# 04__EFR32_Signal_Assign.net
KiCad netlist of a schematic drawn in Altium Designer
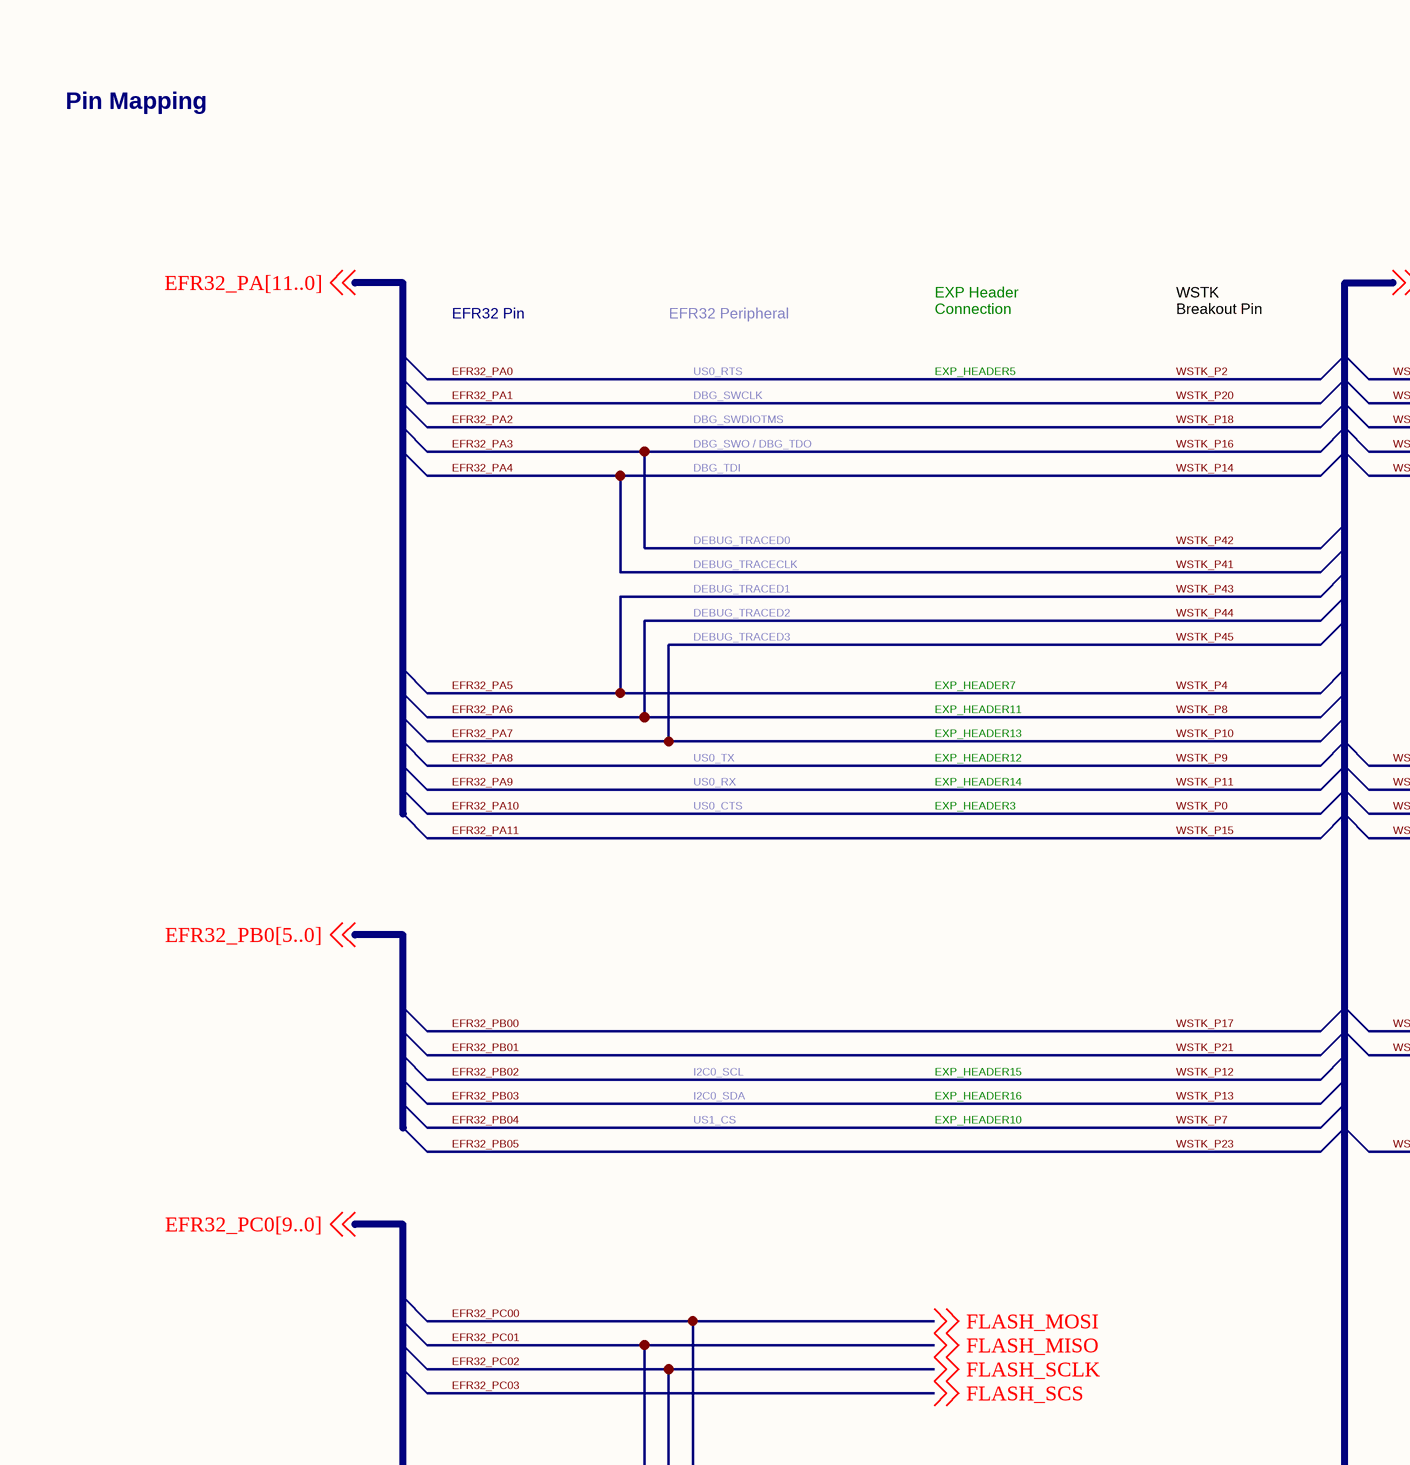
[diagram p0: 04_ EFR32 Signal Assign.SchDoc, top left]
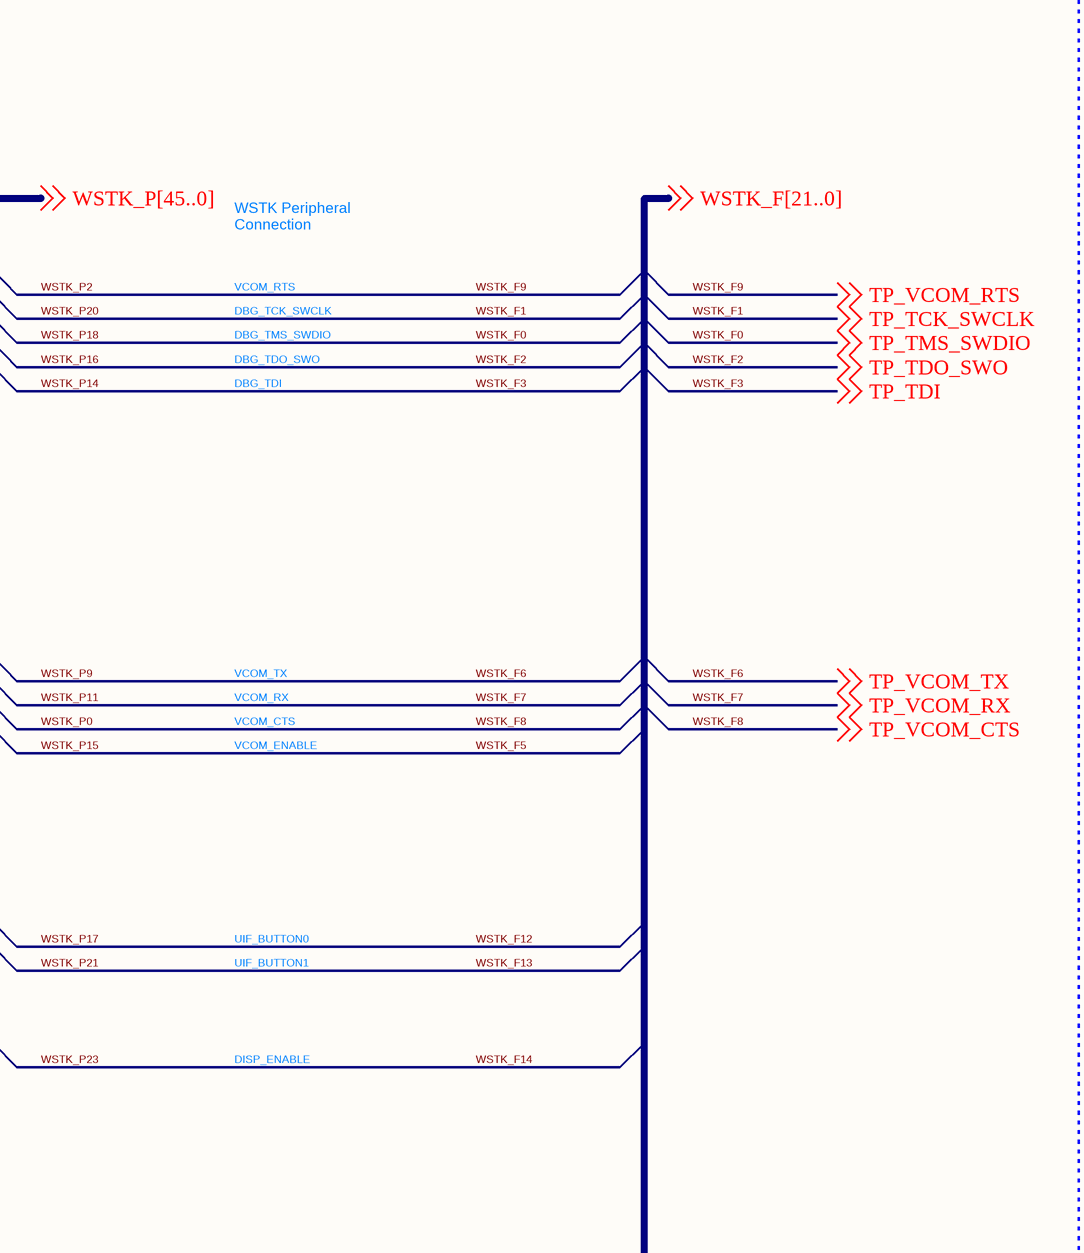
[diagram p1: 04_ EFR32 Signal Assign.SchDoc, top middle]
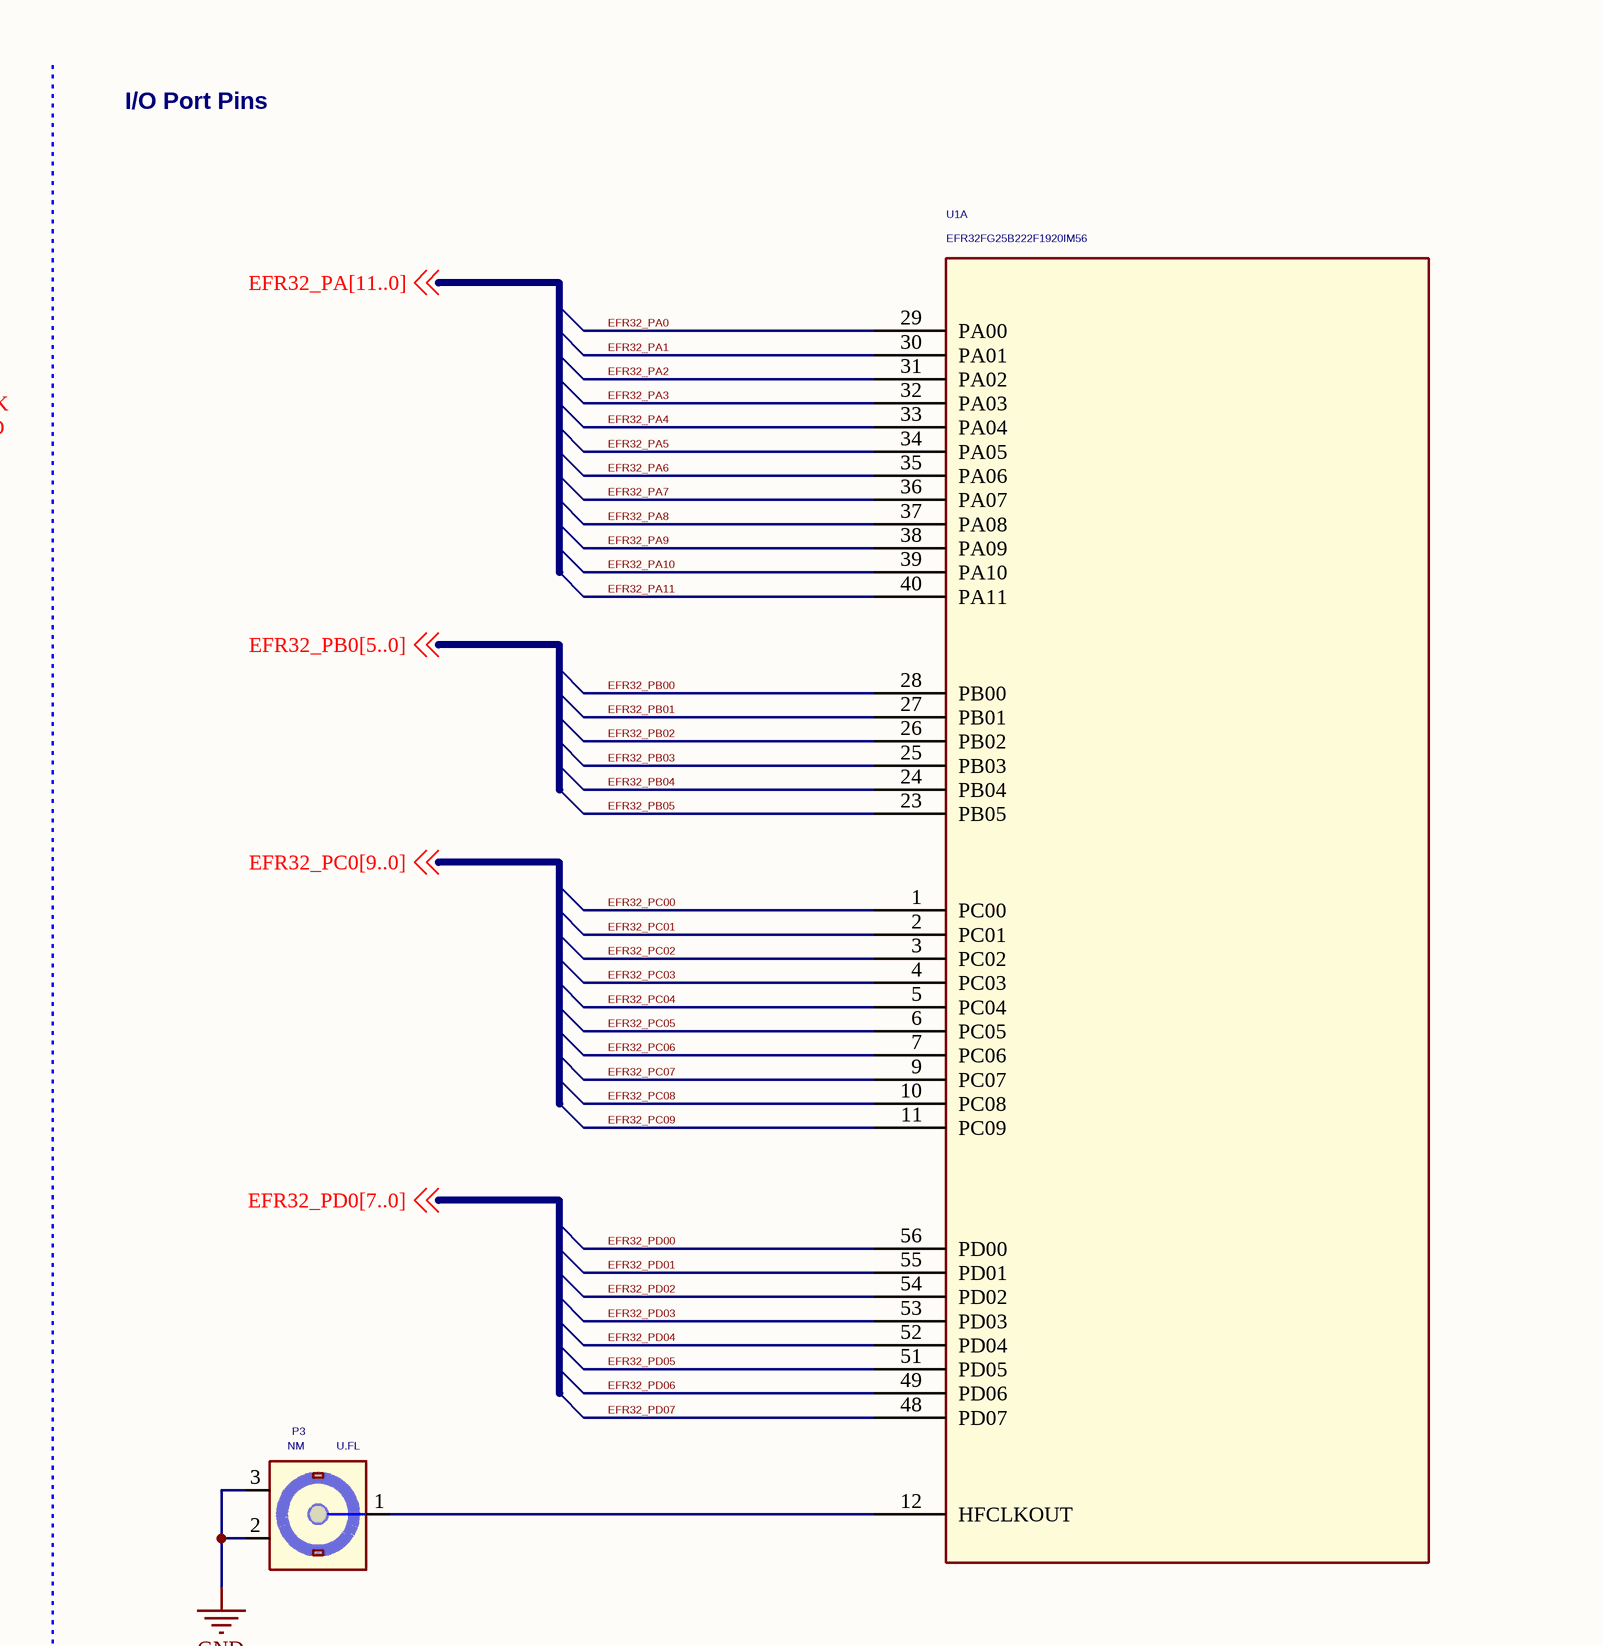
[diagram p2: 04_ EFR32 Signal Assign.SchDoc, top right]
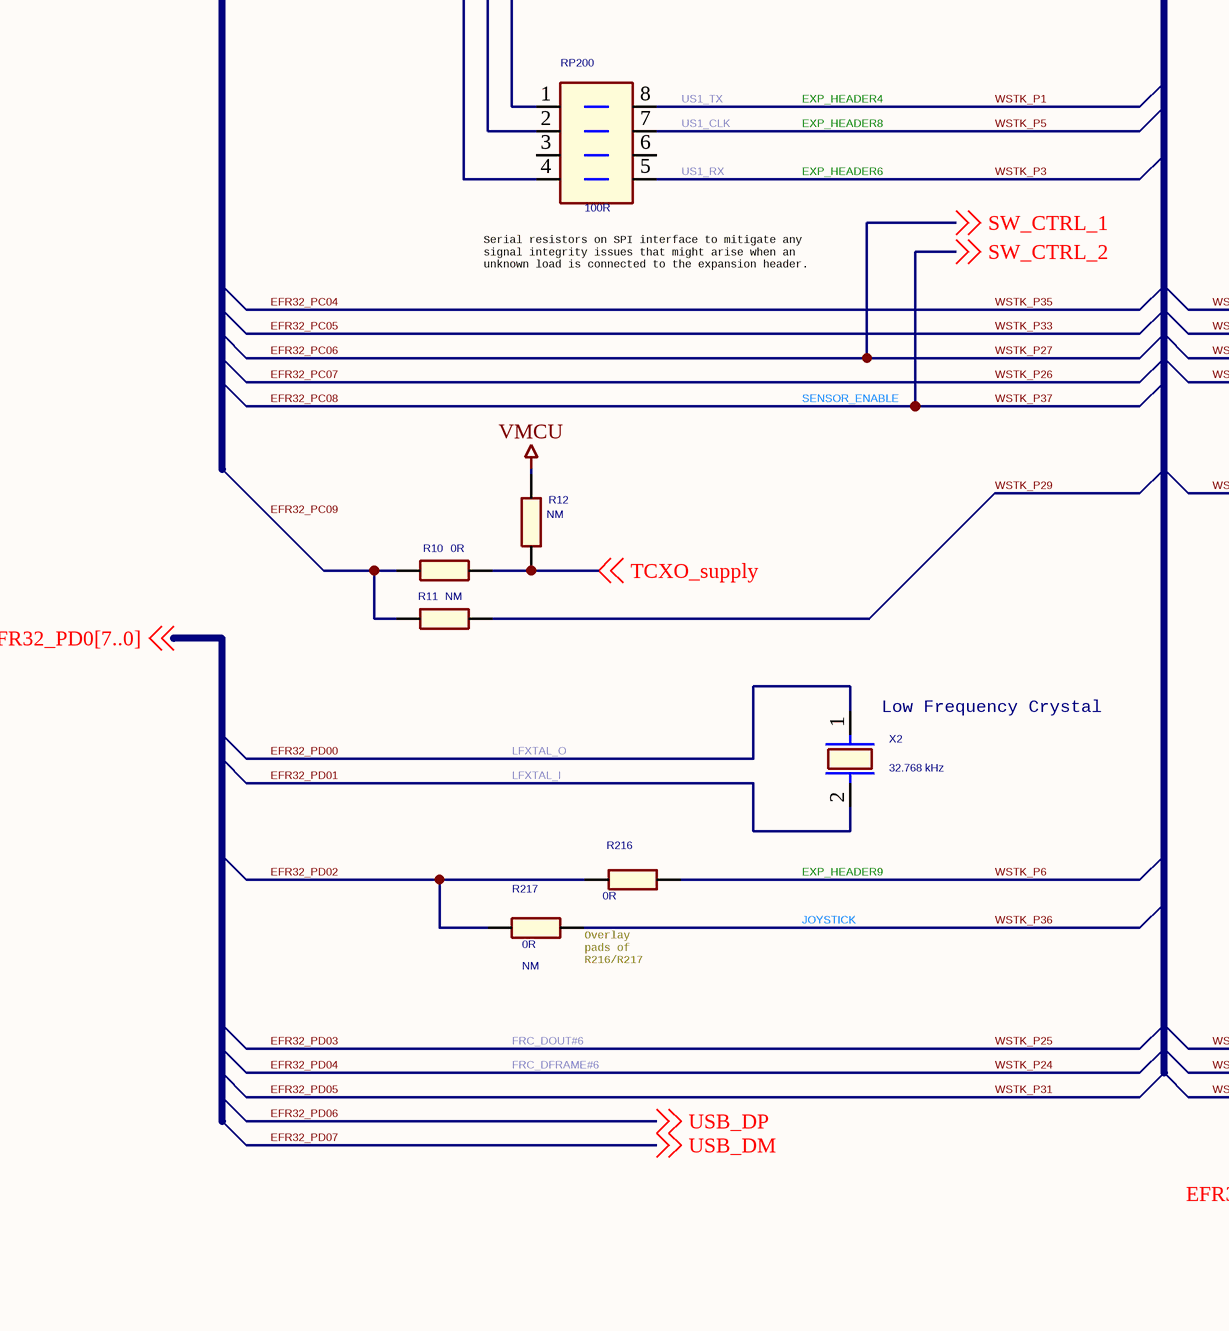
[diagram p3: 04_ EFR32 Signal Assign.SchDoc, bottom left]
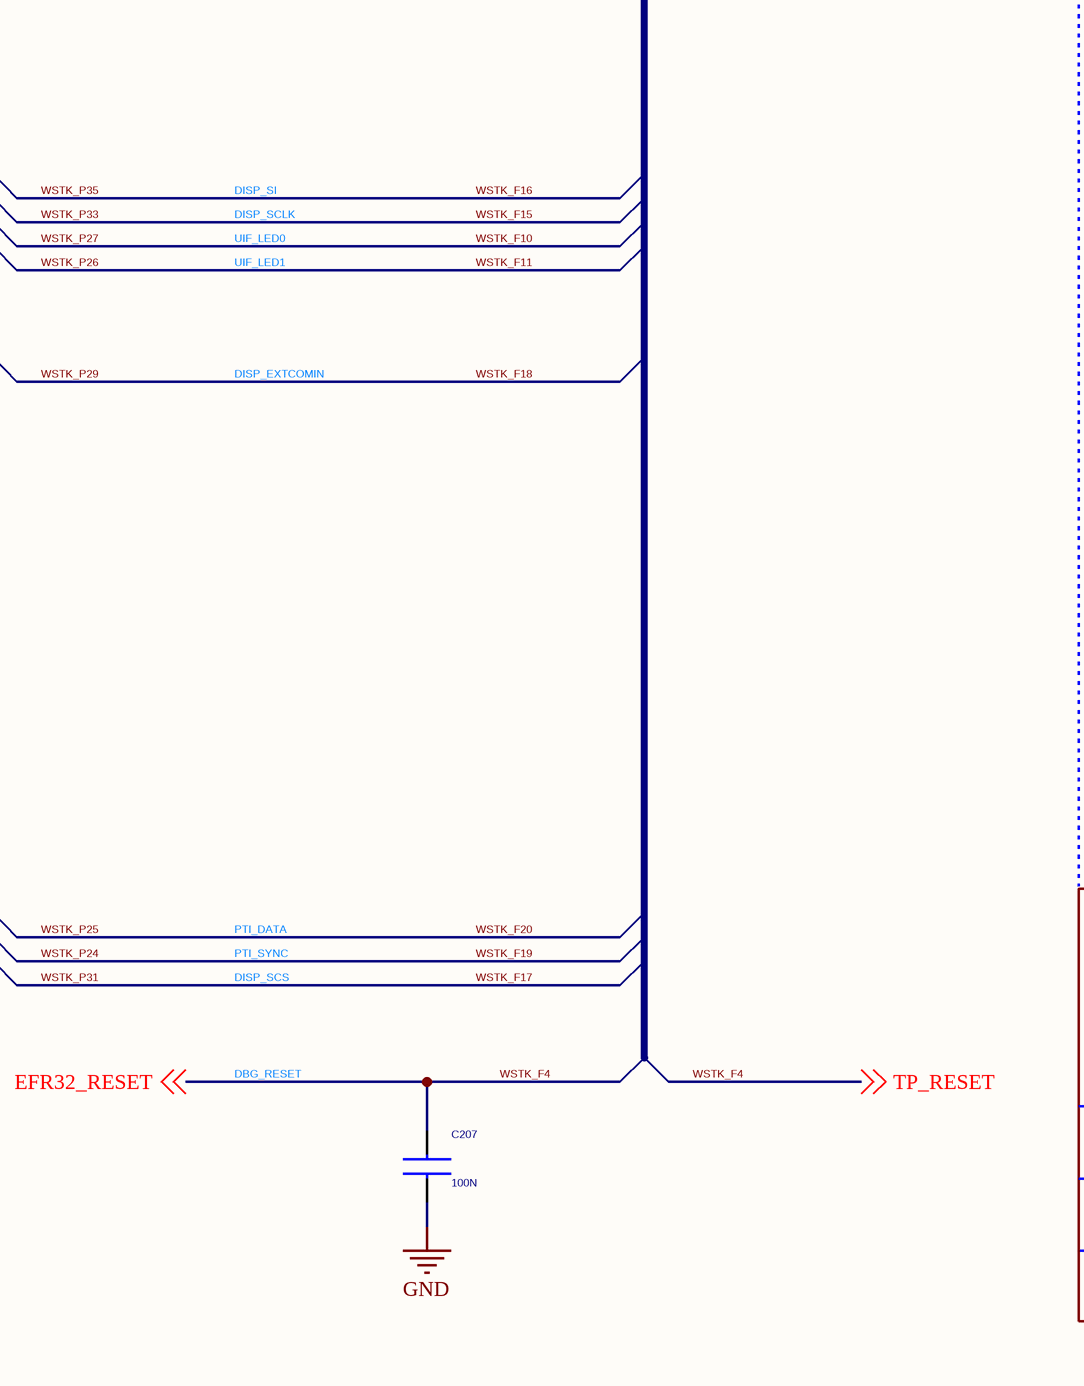
[diagram p4: 04_ EFR32 Signal Assign.SchDoc, bottom middle]
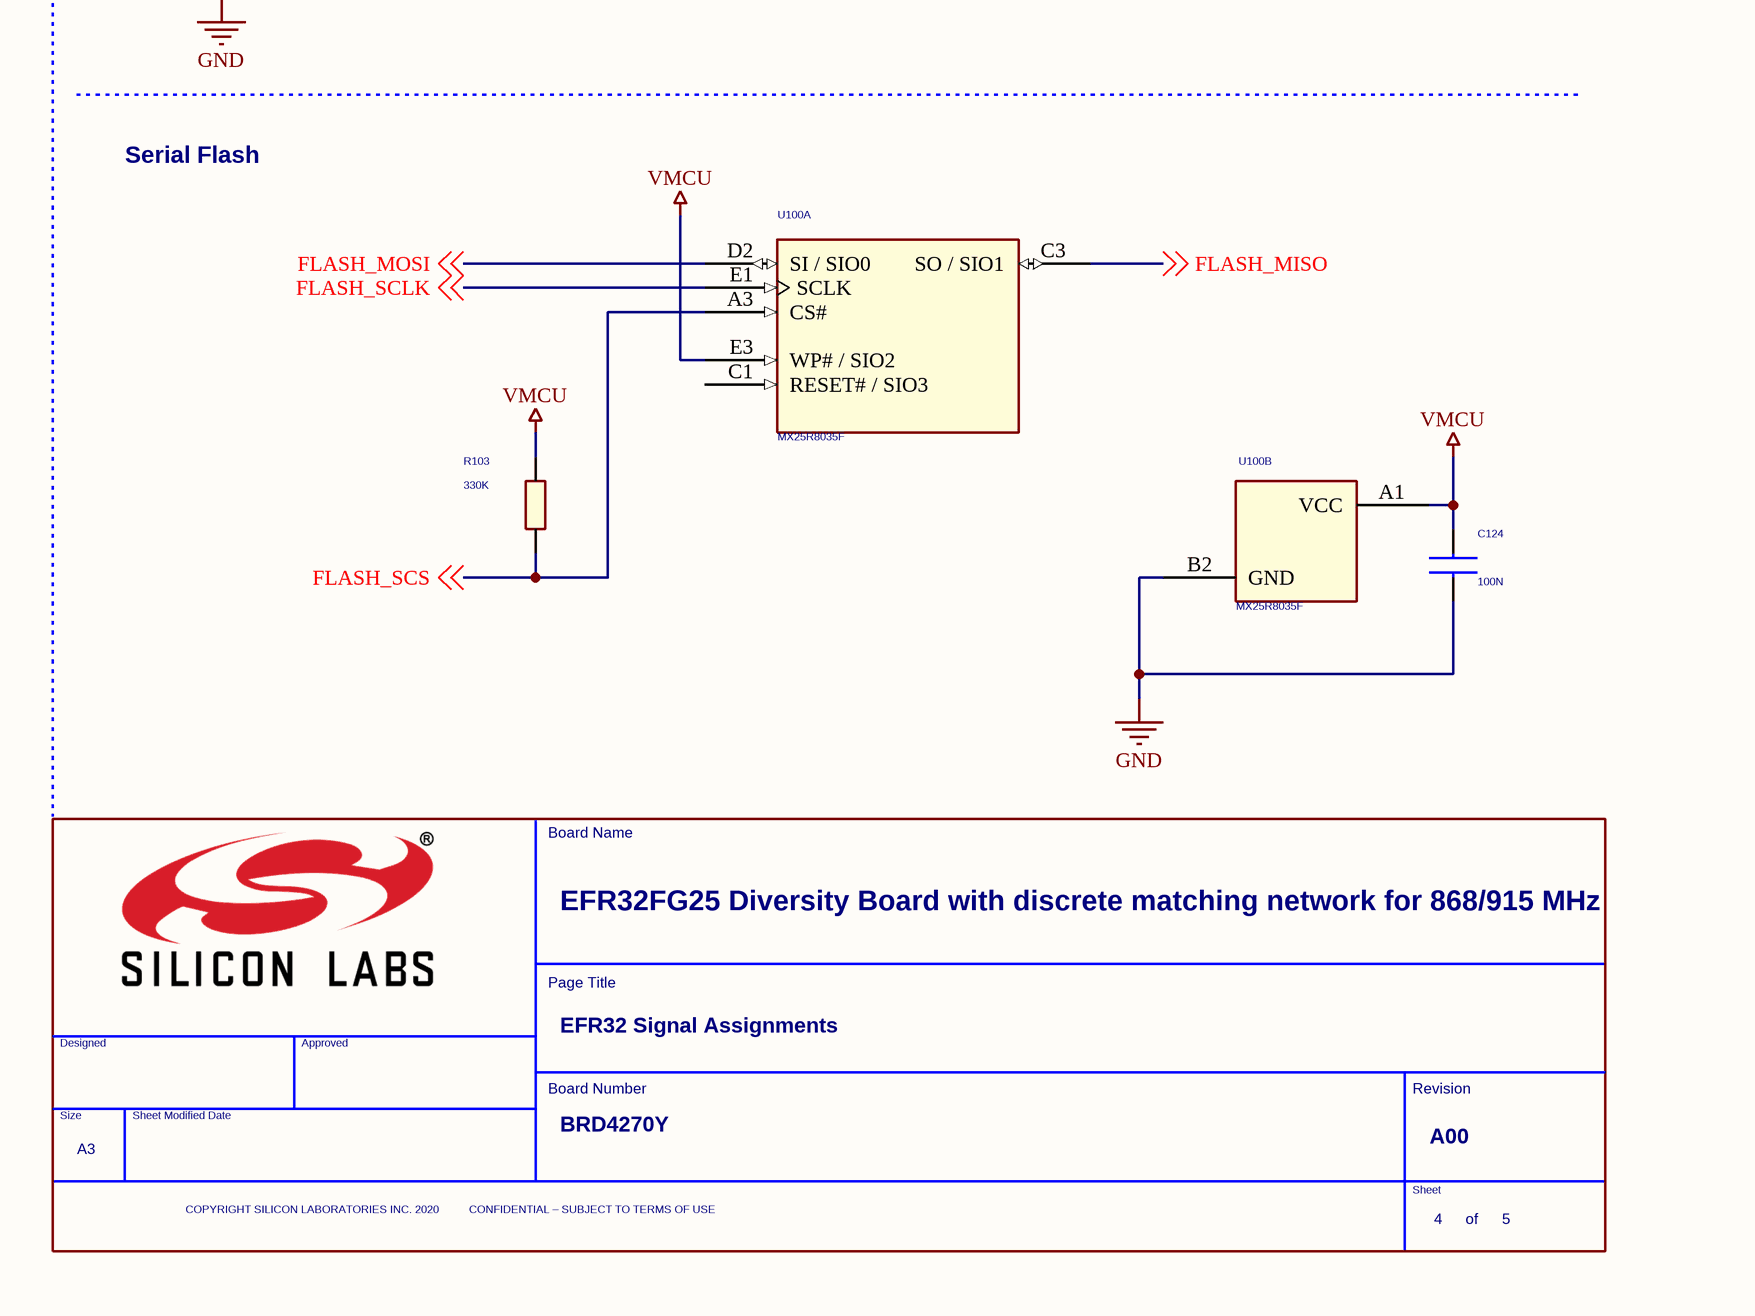
[diagram p5: 04_ EFR32 Signal Assign.SchDoc, bottom right]

(export (version "E")
  (design (tool "Eeschema 10.0.6"))
  (components
    (comp (ref "C124")
      (value "100N")
      (footprint "C0201_L")
      (fields (field (name "TOLERANCE") "20%"))
      (libsource (lib "*") (part "C0201"))
    )
    (comp (ref "C207")
      (value "100N")
      (footprint "C0201_L")
      (fields (field (name "TOLERANCE") "20%"))
      (libsource (lib "*") (part "C0201"))
    )
    (comp (ref "P3")
      (value "U.FL")
      (footprint "HIROSE_U.FL-R-SMT-1")
      (fields (field (name "NOT MOUNTED") "NM") (field (name "MFG") "KLS"))
      (libsource (lib "*") (part "KLS_U.FL"))
    )
    (comp (ref "R10") (value "0R") (footprint "R0402_L") (libsource (lib "") (part "R0402_1")))
    (comp (ref "R11") (value "NM") (footprint "R0402_L") (libsource (lib "") (part "R0402_1")))
    (comp (ref "R12") (value "NM") (footprint "R0402_L") (libsource (lib "*") (part "R0402")))
    (comp (ref "R103") (value "330K") (footprint "R0201_L") (libsource (lib "*") (part "R0201")))
    (comp (ref "R216") (value "0R") (footprint "R0402_L") (libsource (lib "") (part "R0402_1")))
    (comp (ref "R217")
      (value "0R")
      (footprint "R0402_L")
      (fields (field (name "NOT MOUNTED") "NM"))
      (libsource (lib "*") (part "R0402"))
    )
    (comp (ref "RP200")
      (value "100R")
      (footprint "RES_MNR04-8")
      (fields (field (name "MFG") "ROHM"))
      (libsource (lib "*") (part "MNR04M0APJ101"))
    )
    (comp (ref "U1")
      (value "EFR32FG25B222F1920IM56")
      (footprint "QFN56_M040_7.0X7.0_EP_SL")
      (fields (field (name "MFG") "Silicon Labs"))
      (libsource (lib "*") (part "EFR32xG25_QFN56_HFCLKOUT"))
    )
    (comp (ref "U100")
      (value "MX25R8035F")
      (footprint "BGA8_M040_1.24x1.75_WLCSP")
      (fields (field (name "MFG") "Macronix"))
      (libsource (lib "*") (part "MX25R8035"))
    )
    (comp (ref "X2")
      (value "32.768 kHz")
      (footprint "X_MCS_CM8V-T1A")
      (fields (field (name "MFG") "Micro Crystal AG"))
      (libsource (lib "*") (part "CM8V-T1A"))
    )
  )
  (nets
    (net (code "4") (name "EFR32_PC09") (class "Default")
      (node (ref "R10") (pin "2") (pinfunction "2_2") (pintype "passive"))
      (node (ref "R11") (pin "2") (pinfunction "2_2") (pintype "passive"))
      (node (ref "U1") (pin "11") (pinfunction "PC09_11") (pintype "passive"))
    )
    (net (code "5") (name "EFR32_PD00") (class "Default")
      (node (ref "U1") (pin "56") (pinfunction "PD00_56") (pintype "passive"))
      (node (ref "X2") (pin "1") (pinfunction "1_1") (pintype "passive"))
    )
    (net (code "7") (name "EFR32_PD01") (class "Default")
      (node (ref "U1") (pin "55") (pinfunction "PD01_55") (pintype "passive"))
      (node (ref "X2") (pin "2") (pinfunction "2_2") (pintype "passive"))
    )
    (net (code "8") (name "EFR32_PD02") (class "Default")
      (node (ref "R216") (pin "2") (pinfunction "2_2") (pintype "passive"))
      (node (ref "R217") (pin "1") (pinfunction "1_1") (pintype "passive"))
      (node (ref "U1") (pin "54") (pinfunction "PD02_54") (pintype "passive"))
    )
    (net (code "9") (name "EFR32_RESET") (class "Default")
      (node (ref "C207") (pin "1") (pinfunction "1_1") (pintype "passive"))
    )
    (net (code "10") (name "FLASH_MISO") (class "Default")
      (node (ref "RP200") (pin "4") (pinfunction "R14_4") (pintype "passive"))
      (node (ref "U1") (pin "2") (pinfunction "PC01_2") (pintype "passive"))
      (node (ref "U100") (pin "C3") (pinfunction "SO_/_SIO1_C3") (pintype "bidirectional"))
    )
    (net (code "11") (name "FLASH_MOSI") (class "Default")
      (node (ref "RP200") (pin "1") (pinfunction "R11_1") (pintype "passive"))
      (node (ref "U1") (pin "1") (pinfunction "PC00_1") (pintype "passive"))
      (node (ref "U100") (pin "D2") (pinfunction "SI_/_SIO0_D2") (pintype "bidirectional"))
    )
    (net (code "12") (name "FLASH_SCLK") (class "Default")
      (node (ref "RP200") (pin "2") (pinfunction "R12_2") (pintype "passive"))
      (node (ref "U1") (pin "3") (pinfunction "PC02_3") (pintype "passive"))
      (node (ref "U100") (pin "E1") (pinfunction "SCLK_E1") (pintype "input"))
    )
    (net (code "13") (name "FLASH_SCS") (class "Default")
      (node (ref "R103") (pin "1") (pinfunction "1_1") (pintype "passive"))
      (node (ref "U1") (pin "4") (pinfunction "PC03_4") (pintype "passive"))
      (node (ref "U100") (pin "A3") (pinfunction "CS#_A3") (pintype "input"))
    )
    (net (code "14") (name "GND") (class "Default")
      (node (ref "C124") (pin "2") (pinfunction "2_2") (pintype "passive"))
      (node (ref "C207") (pin "2") (pinfunction "2_2") (pintype "passive"))
      (node (ref "P3") (pin "2") (pinfunction "GND1_2") (pintype "passive"))
      (node (ref "P3") (pin "3") (pinfunction "GND4_3") (pintype "passive"))
      (node (ref "U100") (pin "B2") (pinfunction "GND_B2") (pintype "power_in"))
    )
    (net (code "15") (name "Net-(P3-SIGNAL)") (class "Default")
      (node (ref "P3") (pin "1") (pinfunction "SIGNAL_1") (pintype "passive"))
      (node (ref "U1") (pin "12") (pinfunction "HFCLKOUT_12") (pintype "passive"))
    )
    (net (code "16") (name "SW_CTRL_1") (class "Default")
      (node (ref "U1") (pin "7") (pinfunction "PC06_7") (pintype "passive"))
    )
    (net (code "17") (name "SW_CTRL_2") (class "Default")
      (node (ref "U1") (pin "10") (pinfunction "PC08_10") (pintype "passive"))
    )
    (net (code "18") (name "TCXO_supply") (class "Default")
      (node (ref "R10") (pin "1") (pinfunction "1_1") (pintype "passive"))
      (node (ref "R12") (pin "1") (pinfunction "1_1") (pintype "passive"))
    )
    (net (code "19") (name "TP_TCK_SWCLK") (class "Default")
      (node (ref "U1") (pin "30") (pinfunction "PA01_30") (pintype "passive"))
    )
    (net (code "20") (name "TP_TDI") (class "Default")
      (node (ref "U1") (pin "33") (pinfunction "PA04_33") (pintype "passive"))
    )
    (net (code "21") (name "TP_TDO_SWO") (class "Default")
      (node (ref "U1") (pin "32") (pinfunction "PA03_32") (pintype "passive"))
    )
    (net (code "22") (name "TP_TMS_SWDIO") (class "Default")
      (node (ref "U1") (pin "31") (pinfunction "PA02_31") (pintype "passive"))
    )
    (net (code "23") (name "TP_VCOM_CTS") (class "Default")
      (node (ref "U1") (pin "39") (pinfunction "PA10_39") (pintype "passive"))
    )
    (net (code "24") (name "TP_VCOM_RTS") (class "Default")
      (node (ref "U1") (pin "29") (pinfunction "PA00_29") (pintype "passive"))
    )
    (net (code "25") (name "TP_VCOM_RX") (class "Default")
      (node (ref "U1") (pin "38") (pinfunction "PA09_38") (pintype "passive"))
    )
    (net (code "26") (name "TP_VCOM_TX") (class "Default")
      (node (ref "U1") (pin "37") (pinfunction "PA08_37") (pintype "passive"))
    )
    (net (code "27") (name "USB_DM") (class "Default")
      (node (ref "U1") (pin "48") (pinfunction "PD07_48") (pintype "passive"))
    )
    (net (code "28") (name "USB_DP") (class "Default")
      (node (ref "U1") (pin "49") (pinfunction "PD06_49") (pintype "passive"))
    )
    (net (code "29") (name "VMCU") (class "Default")
      (node (ref "C124") (pin "1") (pinfunction "1_1") (pintype "passive"))
      (node (ref "R103") (pin "2") (pinfunction "2_2") (pintype "passive"))
      (node (ref "R12") (pin "2") (pinfunction "2_2") (pintype "passive"))
      (node (ref "U100") (pin "A1") (pinfunction "VCC_A1") (pintype "power_in"))
      (node (ref "U100") (pin "E3") (pinfunction "WP#_/_SIO2_E3") (pintype "input"))
    )
    (net (code "30") (name "WSTK_F5") (class "Default")
      (node (ref "U1") (pin "40") (pinfunction "PA11_40") (pintype "passive"))
    )
    (net (code "31") (name "WSTK_F11") (class "Default")
      (node (ref "U1") (pin "9") (pinfunction "PC07_9") (pintype "passive"))
    )
    (net (code "32") (name "WSTK_F12") (class "Default")
      (node (ref "U1") (pin "28") (pinfunction "PB00_28") (pintype "passive"))
    )
    (net (code "33") (name "WSTK_F13") (class "Default")
      (node (ref "U1") (pin "27") (pinfunction "PB01_27") (pintype "passive"))
    )
    (net (code "34") (name "WSTK_F14") (class "Default")
      (node (ref "U1") (pin "23") (pinfunction "PB05_23") (pintype "passive"))
    )
    (net (code "35") (name "WSTK_F15") (class "Default")
      (node (ref "U1") (pin "6") (pinfunction "PC05_6") (pintype "passive"))
    )
    (net (code "36") (name "WSTK_F16") (class "Default")
      (node (ref "U1") (pin "5") (pinfunction "PC04_5") (pintype "passive"))
    )
    (net (code "37") (name "WSTK_F17") (class "Default")
      (node (ref "U1") (pin "51") (pinfunction "PD05_51") (pintype "passive"))
    )
    (net (code "38") (name "WSTK_F18") (class "Default")
      (node (ref "R11") (pin "1") (pinfunction "1_1") (pintype "passive"))
    )
    (net (code "39") (name "WSTK_F19") (class "Default")
      (node (ref "U1") (pin "52") (pinfunction "PD04_52") (pintype "passive"))
    )
    (net (code "40") (name "WSTK_F20") (class "Default")
      (node (ref "U1") (pin "53") (pinfunction "PD03_53") (pintype "passive"))
    )
    (net (code "42") (name "WSTK_P1") (class "Default")
      (node (ref "RP200") (pin "8") (pinfunction "R18_8") (pintype "passive"))
    )
    (net (code "43") (name "WSTK_P3") (class "Default")
      (node (ref "RP200") (pin "5") (pinfunction "R15_5") (pintype "passive"))
    )
    (net (code "44") (name "WSTK_P5") (class "Default")
      (node (ref "RP200") (pin "7") (pinfunction "R17_7") (pintype "passive"))
    )
    (net (code "45") (name "WSTK_P6") (class "Default")
      (node (ref "R216") (pin "1") (pinfunction "1_1") (pintype "passive"))
    )
    (net (code "46") (name "WSTK_P7") (class "Default")
      (node (ref "U1") (pin "24") (pinfunction "PB04_24") (pintype "passive"))
    )
    (net (code "47") (name "WSTK_P8") (class "Default")
      (node (ref "U1") (pin "35") (pinfunction "PA06_35") (pintype "passive"))
    )
    (net (code "48") (name "WSTK_P12") (class "Default")
      (node (ref "U1") (pin "26") (pinfunction "PB02_26") (pintype "passive"))
    )
    (net (code "49") (name "WSTK_P13") (class "Default")
      (node (ref "U1") (pin "25") (pinfunction "PB03_25") (pintype "passive"))
    )
    (net (code "50") (name "WSTK_P36") (class "Default")
      (node (ref "R217") (pin "2") (pinfunction "2_2") (pintype "passive"))
    )
    (net (code "51") (name "WSTK_P43") (class "Default")
      (node (ref "U1") (pin "34") (pinfunction "PA05_34") (pintype "passive"))
    )
    (net (code "52") (name "WSTK_P45") (class "Default")
      (node (ref "U1") (pin "36") (pinfunction "PA07_36") (pintype "passive"))
    )
    (net (code "54") (name "unconnected-(RP200-R13-Pad3)") (class "Default")
      (node (ref "RP200") (pin "3") (pinfunction "R13_3") (pintype "passive"))
    )
    (net (code "55") (name "unconnected-(RP200-R16-Pad6)") (class "Default")
      (node (ref "RP200") (pin "6") (pinfunction "R16_6") (pintype "passive"))
    )
    (net (code "56") (name "unconnected-(U100A-RESET#_{slash}_SIO3-PadC1)") (class "Default")
      (node (ref "U100") (pin "C1") (pinfunction "RESET#_/_SIO3_C1") (pintype "input"))
    )
  )
)
